# TempProbeProgrammer.net
KiCad netlist of a schematic drawn in EAGLE
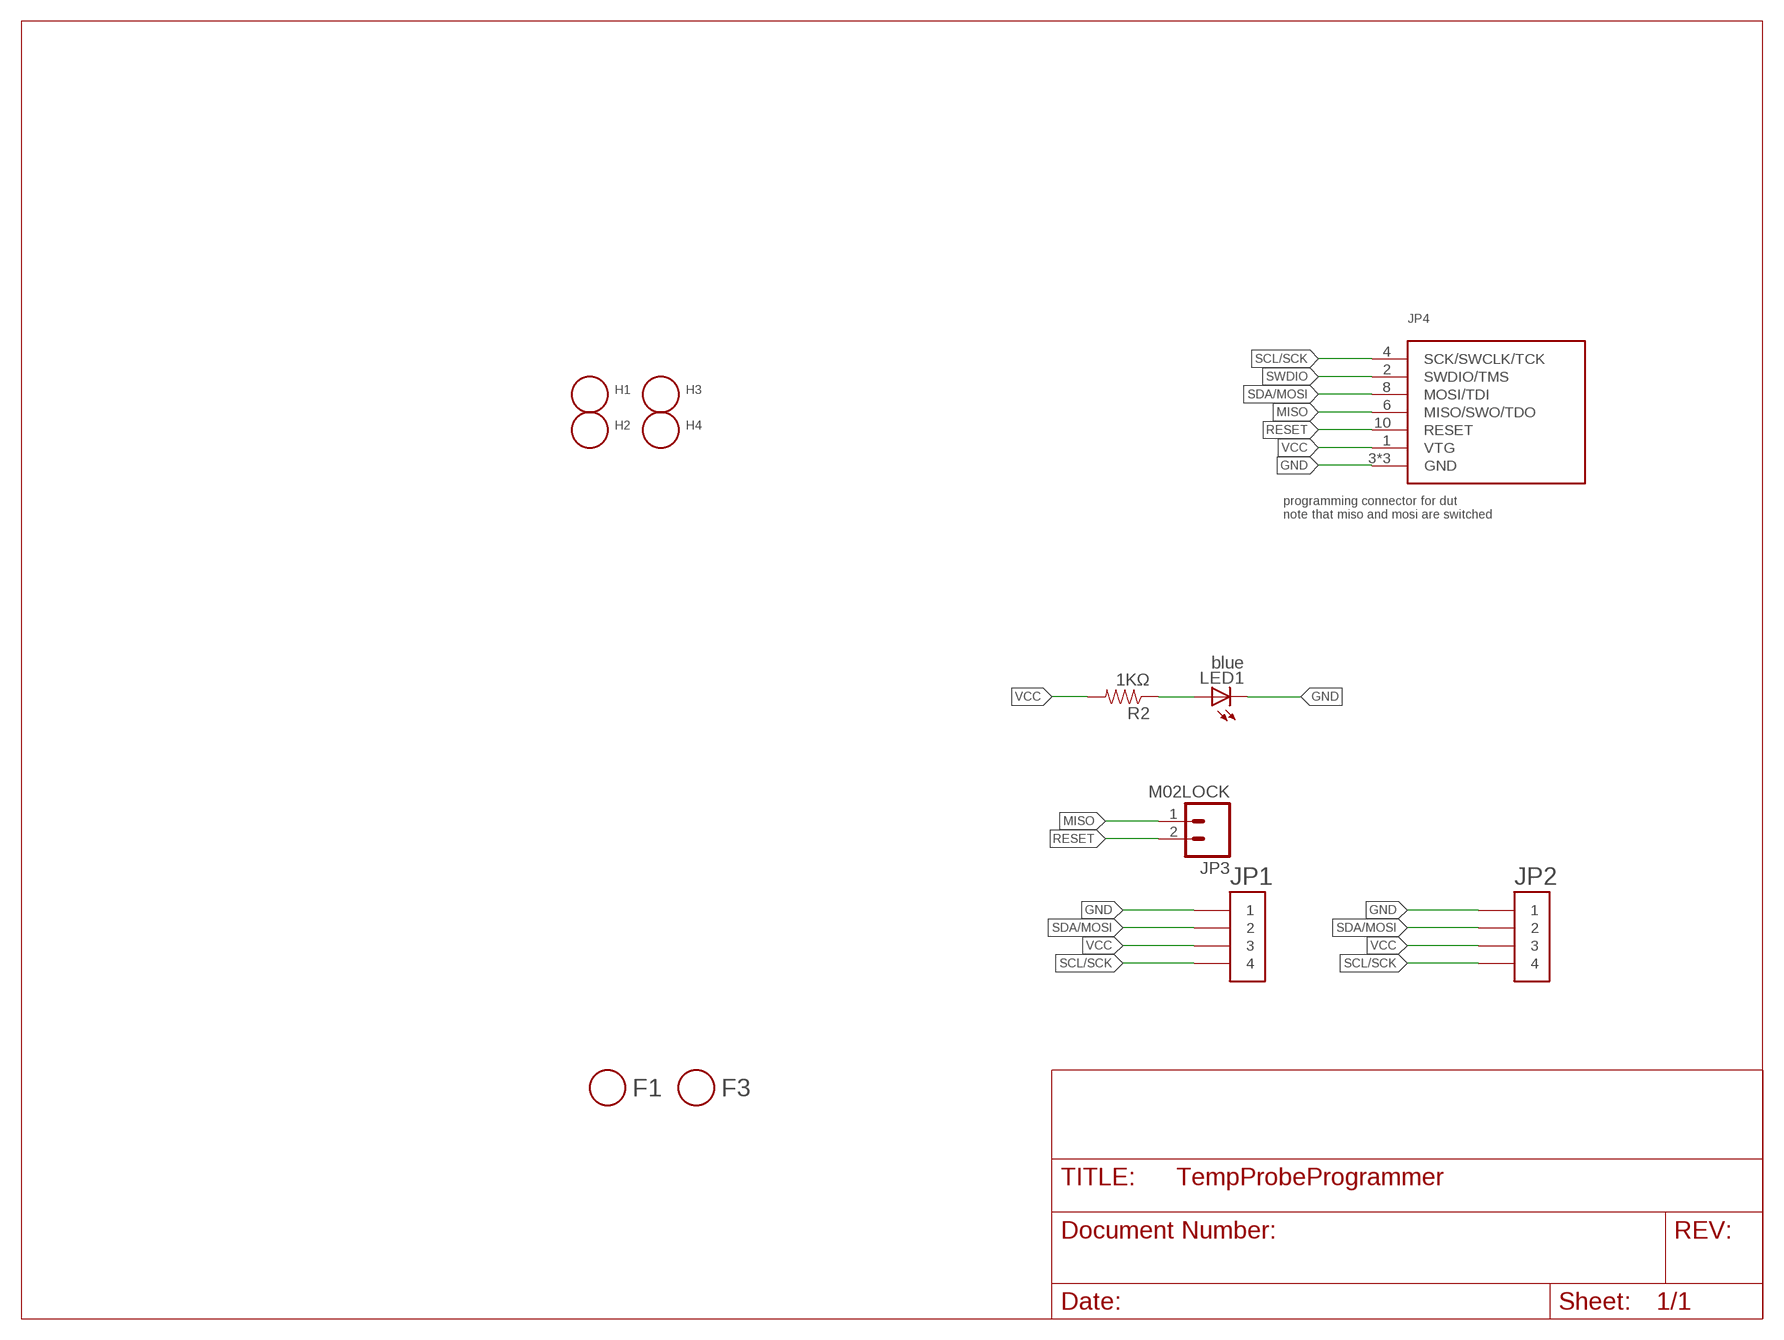
[diagram p0: schematic, sheet 1]

(export (version "E")
  (design (tool "Eeschema 10.0.6"))
  (components
    (comp (ref "F1")
      (value "FIDUCIAL")
      (footprint "eagle-import:FIDUCIAL_1MM")
      (libsource (lib "eagle-import") (part "FIDUCIAL"))
    )
    (comp (ref "F3")
      (value "FIDUCIAL")
      (footprint "eagle-import:FIDUCIAL_1MM")
      (libsource (lib "eagle-import") (part "FIDUCIAL"))
    )
    (comp (ref "H1")
      (value "HOLE#4")
      (footprint "eagle-import:HOLE-#4")
      (fields (field (name "PARTNUM") "EXCLUDE"))
      (libsource (lib "eagle-import") (part "HOLE#4"))
    )
    (comp (ref "H2")
      (value "HOLE#4")
      (footprint "eagle-import:HOLE-#4")
      (fields (field (name "PARTNUM") "EXCLUDE"))
      (libsource (lib "eagle-import") (part "HOLE#4"))
    )
    (comp (ref "H3")
      (value "HOLE#4")
      (footprint "eagle-import:HOLE-#4")
      (fields (field (name "PARTNUM") "EXCLUDE"))
      (libsource (lib "eagle-import") (part "HOLE#4"))
    )
    (comp (ref "H4")
      (value "HOLE#4")
      (footprint "eagle-import:HOLE-#4")
      (fields (field (name "PARTNUM") "EXCLUDE"))
      (libsource (lib "eagle-import") (part "HOLE#4"))
    )
    (comp (ref "JP1")
      (value "HEADER-1X4-JST-PA-SIDE-SMD")
      (footprint "eagle-import:JST-PA-SIDE-SMD")
      (fields (field (name "PARTNUM") "SM04B-PASS-TBT(LF)(SN)"))
      (libsource (lib "eagle-import") (part "HEADER-1X4-JST-PA-SIDE-SMD"))
    )
    (comp (ref "JP2")
      (value "HEADER-1X4-JST-PA-SIDE-SMD")
      (footprint "eagle-import:JST-PA-SIDE-SMD")
      (fields (field (name "PARTNUM") "SM04B-PASS-TBT(LF)(SN)"))
      (libsource (lib "eagle-import") (part "HEADER-1X4-JST-PA-SIDE-SMD"))
    )
    (comp (ref "JP3")
      (value "M02LOCK")
      (footprint "eagle-import:1X02_LOCK")
      (fields (field (name "PARTNUM") "EXCLUDE"))
      (libsource (lib "eagle-import") (part "M02LOCK"))
    )
    (comp (ref "JP4")
      (value "ICSP")
      (footprint "eagle-import:2X5-.05")
      (libsource (lib "eagle-import") (part "ICSP"))
    )
    (comp (ref "LED1")
      (value "blue")
      (footprint "eagle-import:0805-LED")
      (fields (field (name "PARTNUM") "LTST-C171TBKT"))
      (libsource (lib "eagle-import") (part "LED-0805-BLUE"))
    )
    (comp (ref "R2")
      (value "1KΩ")
      (footprint "eagle-import:0603")
      (fields (field (name "PARTNUM") "ERJ-3EKF1001V"))
      (libsource (lib "eagle-import") (part "RESISTOR-1KΩ"))
    )
  )
  (nets
    (net (code "1") (name "GND") (class "Default")
      (node (ref "JP1") (pin "1") (pinfunction "1_1") (pintype "bidirectional"))
      (node (ref "JP2") (pin "1") (pinfunction "1_1") (pintype "bidirectional"))
      (node (ref "JP4") (pin "3") (pinfunction "GND_3") (pintype "bidirectional"))
      (node (ref "JP4") (pin "5") (pinfunction "GND_5") (pintype "bidirectional"))
      (node (ref "JP4") (pin "9") (pinfunction "GND_9") (pintype "bidirectional"))
      (node (ref "LED1") (pin "C") (pinfunction "C_C") (pintype "passive"))
    )
    (net (code "2") (name "MISO") (class "Default")
      (node (ref "JP3") (pin "1") (pinfunction "1_1") (pintype "passive"))
      (node (ref "JP4") (pin "6") (pinfunction "MISO/SWO/TDO_6") (pintype "bidirectional"))
    )
    (net (code "3") (name "Net-(LED1-PadA)") (class "Default")
      (node (ref "LED1") (pin "A") (pinfunction "A_A") (pintype "passive"))
      (node (ref "R2") (pin "1") (pinfunction "1_1") (pintype "passive"))
    )
    (net (code "4") (name "RESET") (class "Default")
      (node (ref "JP3") (pin "2") (pinfunction "2_2") (pintype "passive"))
      (node (ref "JP4") (pin "10") (pinfunction "RESET_10") (pintype "bidirectional"))
    )
    (net (code "5") (name "SCL{slash}SCK") (class "Default")
      (node (ref "JP1") (pin "4") (pinfunction "4_4") (pintype "bidirectional"))
      (node (ref "JP2") (pin "4") (pinfunction "4_4") (pintype "bidirectional"))
      (node (ref "JP4") (pin "4") (pinfunction "SCK/SWCLK/TCK_4") (pintype "bidirectional"))
    )
    (net (code "6") (name "SDA{slash}MOSI") (class "Default")
      (node (ref "JP1") (pin "2") (pinfunction "2_2") (pintype "bidirectional"))
      (node (ref "JP2") (pin "2") (pinfunction "2_2") (pintype "bidirectional"))
      (node (ref "JP4") (pin "8") (pinfunction "MOSI/TDI_8") (pintype "bidirectional"))
    )
    (net (code "7") (name "SWDIO") (class "Default")
      (node (ref "JP4") (pin "2") (pinfunction "SWDIO/TMS_2") (pintype "bidirectional"))
    )
    (net (code "8") (name "VCC") (class "Default")
      (node (ref "JP1") (pin "3") (pinfunction "3_3") (pintype "bidirectional"))
      (node (ref "JP2") (pin "3") (pinfunction "3_3") (pintype "bidirectional"))
      (node (ref "JP4") (pin "1") (pinfunction "VTG_1") (pintype "bidirectional"))
      (node (ref "R2") (pin "2") (pinfunction "2_2") (pintype "passive"))
    )
    (net (code "9") (name "unconnected-(H1-HOLE-PadP$1)") (class "Default")
      (node (ref "H1") (pin "P$1") (pinfunction "HOLE_P$1") (pintype "bidirectional"))
    )
    (net (code "10") (name "unconnected-(H2-HOLE-PadP$1)") (class "Default")
      (node (ref "H2") (pin "P$1") (pinfunction "HOLE_P$1") (pintype "bidirectional"))
    )
    (net (code "11") (name "unconnected-(H3-HOLE-PadP$1)") (class "Default")
      (node (ref "H3") (pin "P$1") (pinfunction "HOLE_P$1") (pintype "bidirectional"))
    )
    (net (code "12") (name "unconnected-(H4-HOLE-PadP$1)") (class "Default")
      (node (ref "H4") (pin "P$1") (pinfunction "HOLE_P$1") (pintype "bidirectional"))
    )
  )
)
